# water_counter.net
KiCad netlist of a schematic drawn in EasyEDA
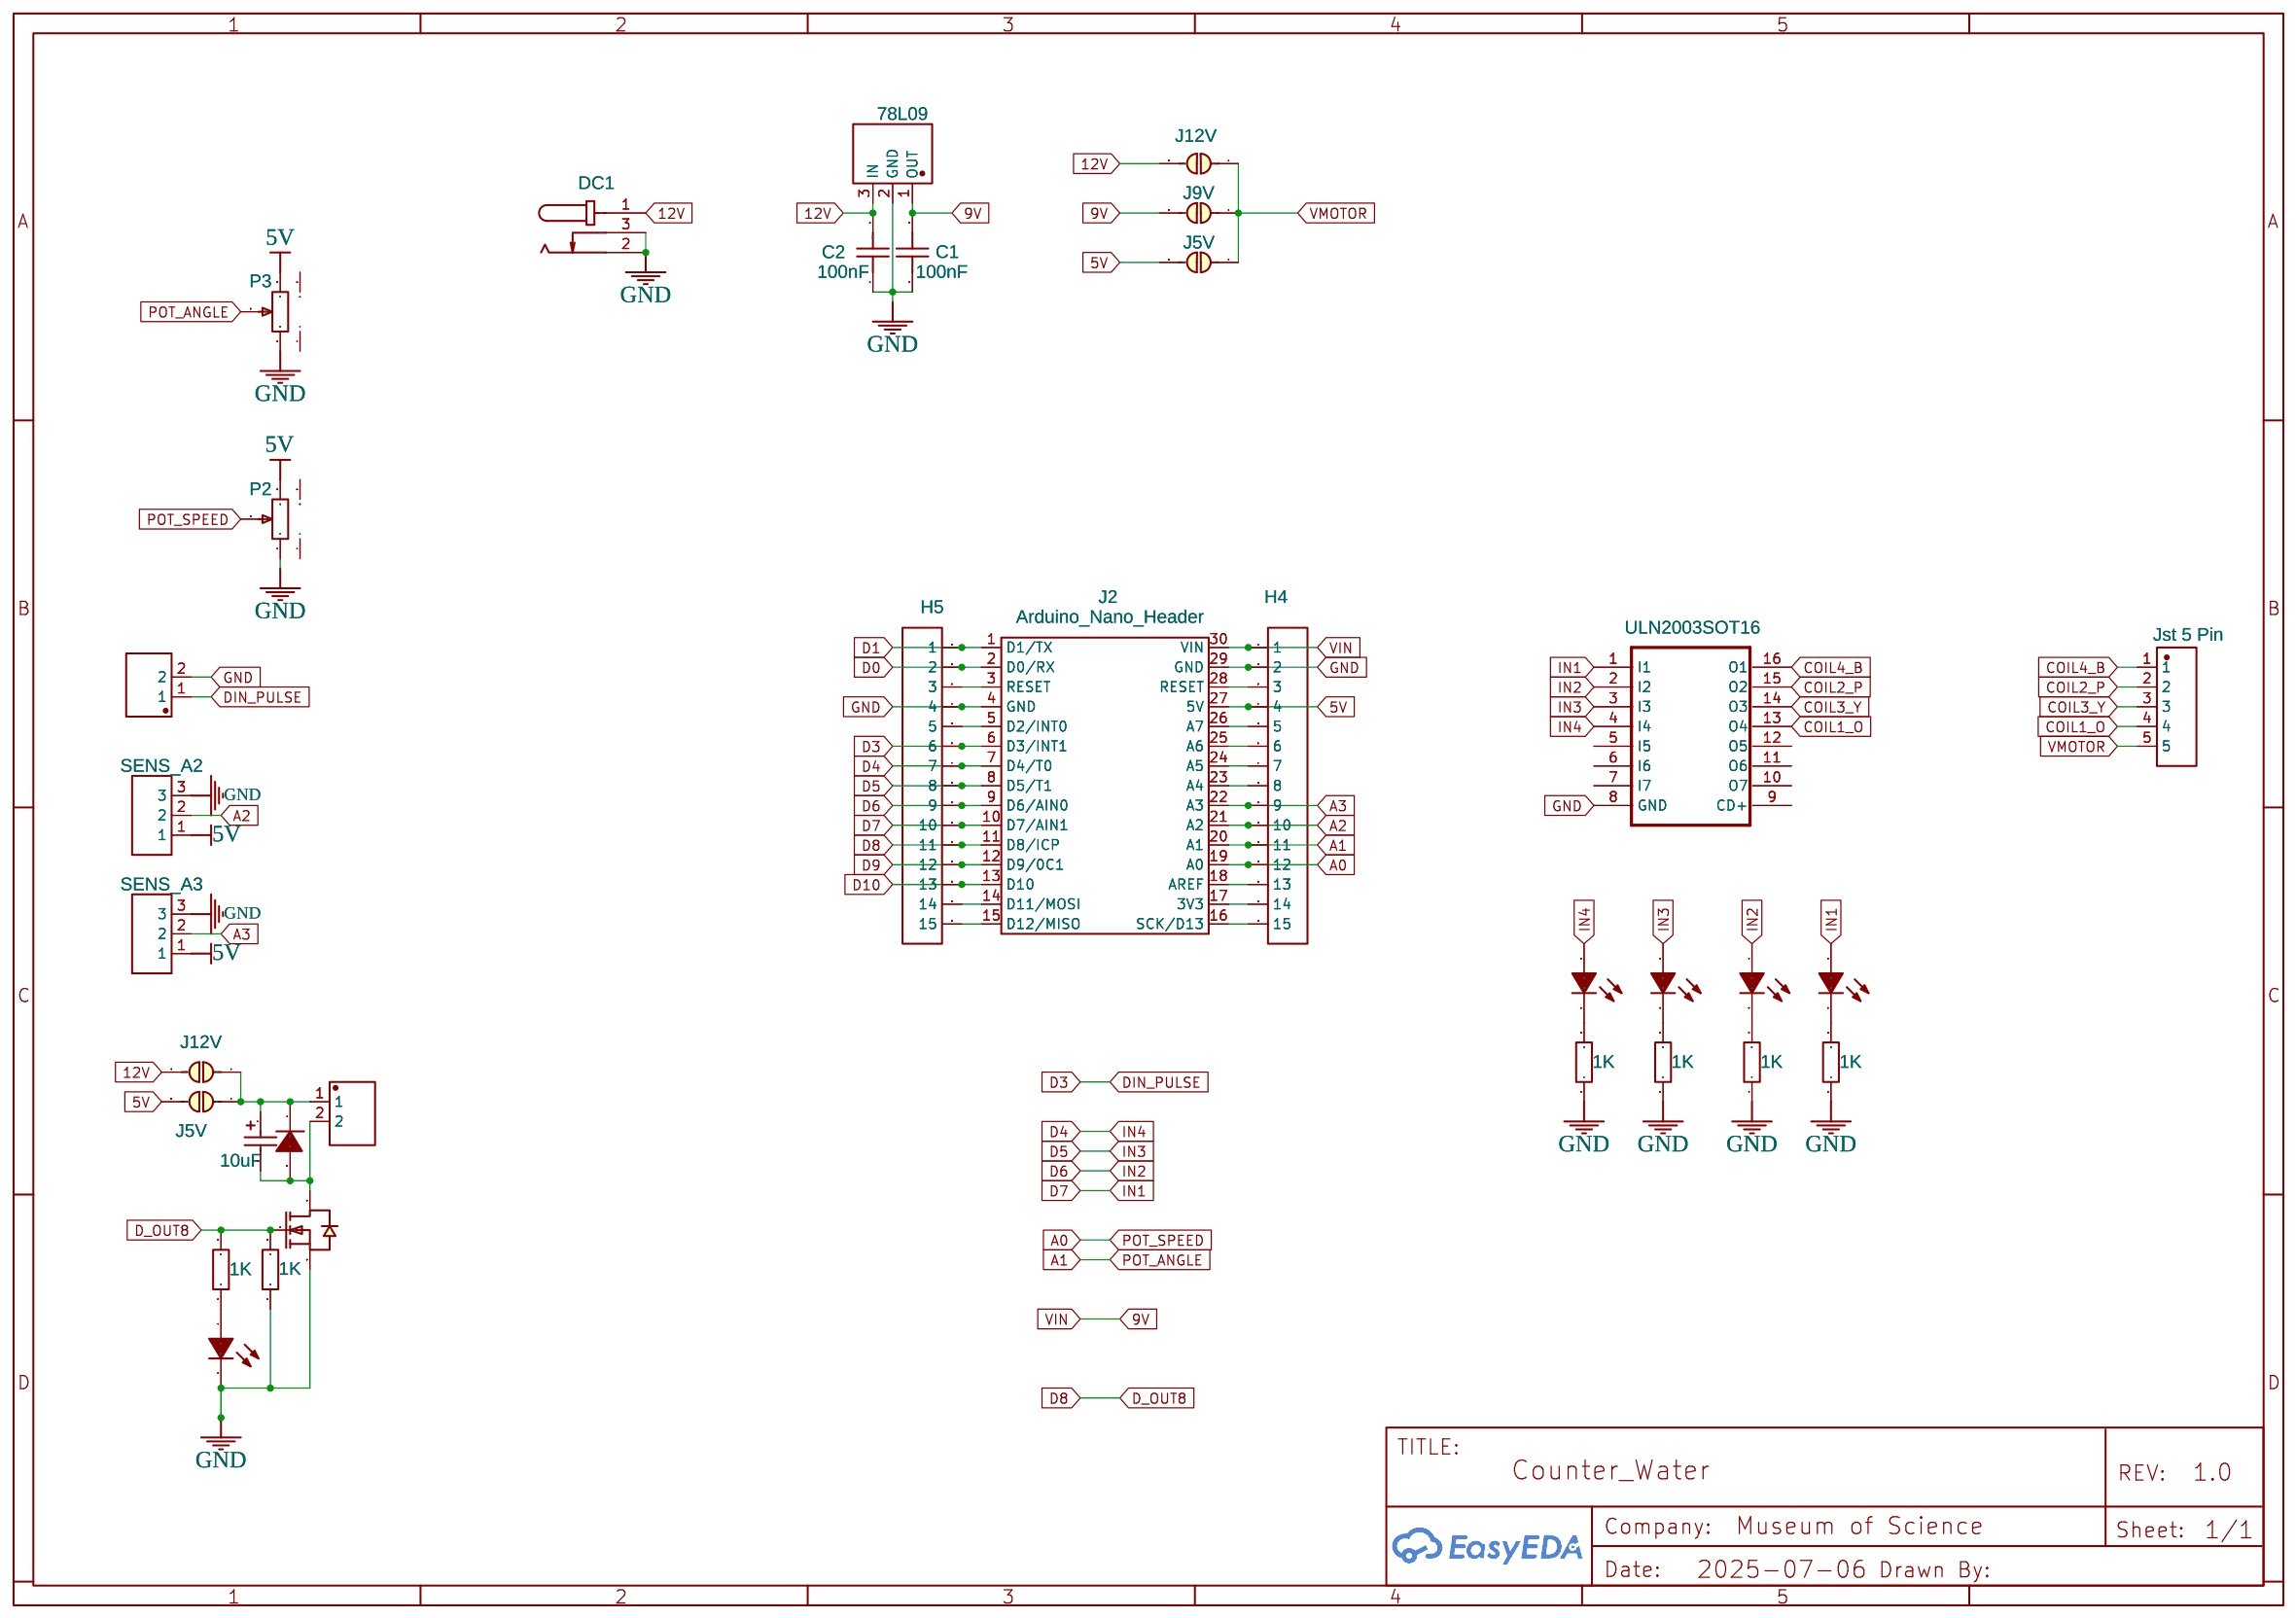
[diagram p0: schematic sheet]

(export (version "E")
  (design (tool "Eeschema 10.0.6"))
  (components
    (comp (ref "C1") (value "100nF") (libsource (lib "") (part "CC0603KRX7R9BB104")))
    (comp (ref "C2") (value "100nF") (libsource (lib "") (part "CC0603KRX7R9BB104")))
    (comp (ref "D3_PULSE")
      (value "KF2510-2A")
      (fields (field (name "Manufacturer") "BOOMELE"))
      (libsource (lib "") (part "KF2510-2A_1"))
    )
    (comp (ref "DC1")
      (value "DC")
      (fields (field (name "Manufacturer Part") "DC005-2.0MM") (field (name "Manufacturer") "SOFNG"))
      (libsource (lib "") (part "DC005-2.0MM"))
    )
    (comp (ref "ECM1") (value "10uF") (libsource (lib "") (part "TAJA106K016RNJ")))
    (comp (ref "ECON1")
      (value "D_OUT8")
      (fields (field (name "Manufacturer Part") "KF2510-2A") (field (name "Manufacturer") "BOOMELE"))
      (libsource (lib "") (part "KF2510-2A"))
    )
    (comp (ref "EDM1")
      (value "1N4007")
      (fields (field (name "Manufacturer Part") "1N4007F") (field (name "Manufacturer") "SK"))
      (libsource (lib "") (part "1N4007F"))
    )
    (comp (ref "ELD1")
      (value "LED")
      (fields
        (field (name "Manufacturer Part") "19-217/BHC-ZL1M2RY/3T")
        (field (name "Manufacturer") "EVERLIGHT")
      )
      (libsource (lib "") (part "19-217/BHC-ZL1M2RY/3T"))
    )
    (comp (ref "ELD2")
      (value "LED")
      (fields
        (field (name "Manufacturer Part") "19-217/BHC-ZL1M2RY/3T")
        (field (name "Manufacturer") "EVERLIGHT")
      )
      (libsource (lib "") (part "19-217/BHC-ZL1M2RY/3T"))
    )
    (comp (ref "ELD3")
      (value "LED")
      (fields
        (field (name "Manufacturer Part") "19-217/BHC-ZL1M2RY/3T")
        (field (name "Manufacturer") "EVERLIGHT")
      )
      (libsource (lib "") (part "19-217/BHC-ZL1M2RY/3T"))
    )
    (comp (ref "ELD4")
      (value "LED")
      (fields
        (field (name "Manufacturer Part") "19-217/BHC-ZL1M2RY/3T")
        (field (name "Manufacturer") "EVERLIGHT")
      )
      (libsource (lib "") (part "19-217/BHC-ZL1M2RY/3T"))
    )
    (comp (ref "ELD5")
      (value "LED")
      (fields
        (field (name "Manufacturer Part") "19-217/BHC-ZL1M2RY/3T")
        (field (name "Manufacturer") "EVERLIGHT")
      )
      (libsource (lib "") (part "19-217/BHC-ZL1M2RY/3T"))
    )
    (comp (ref "EQ1")
      (value "Q")
      (fields (field (name "Manufacturer Part") "AO3400") (field (name "Manufacturer") "ElecSuper(静芯微）"))
      (libsource (lib "") (part "JSM2302"))
    )
    (comp (ref "ERG1")
      (value "1K")
      (fields (field (name "Manufacturer Part") "0603WAF1001T5E") (field (name "Manufacturer") "UniOhm"))
      (libsource (lib "") (part "0603WAF1001T5E_1"))
    )
    (comp (ref "ERL1")
      (value "1K")
      (fields (field (name "Manufacturer Part") "0603WAF1001T5E") (field (name "Manufacturer") "UniOhm"))
      (libsource (lib "") (part "0603WAF1001T5E"))
    )
    (comp (ref "ERL2")
      (value "1K")
      (fields (field (name "Manufacturer Part") "0603WAF1001T5E") (field (name "Manufacturer") "UniOhm"))
      (libsource (lib "") (part "0603WAF1001T5E"))
    )
    (comp (ref "ERL3")
      (value "1K")
      (fields (field (name "Manufacturer Part") "0603WAF1001T5E") (field (name "Manufacturer") "UniOhm"))
      (libsource (lib "") (part "0603WAF1001T5E"))
    )
    (comp (ref "ERL4")
      (value "1K")
      (fields (field (name "Manufacturer Part") "0603WAF1001T5E") (field (name "Manufacturer") "UniOhm"))
      (libsource (lib "") (part "0603WAF1001T5E"))
    )
    (comp (ref "ERL5")
      (value "1K")
      (fields (field (name "Manufacturer Part") "0603WAF1001T5E") (field (name "Manufacturer") "UniOhm"))
      (libsource (lib "") (part "0603WAF1001T5E"))
    )
    (comp (ref "H4") (value "HDR-F-2.54_1x15") (libsource (lib "") (part "HDR-F-2.54_1x15_1")))
    (comp (ref "H5") (value "HDR-F-2.54_1x15") (libsource (lib "") (part "HDR-F-2.54_1x15")))
    (comp (ref "IC1") (value "ULN2003SOT16") (libsource (lib "") (part "ULN2003SOT16")))
    (comp (ref "J2") (value "Arduino_Nano_Header") (libsource (lib "") (part "Arduino_Nano_Header")))
    (comp (ref "J5V_1") (value "J5V") (libsource (lib "") (part "JUMPER-SMT_2_2")))
    (comp (ref "J5V_2") (value "J5V") (libsource (lib "") (part "JUMPER-SMT_2_2")))
    (comp (ref "J9V_1") (value "J9V") (libsource (lib "") (part "JUMPER-SMT_2_1")))
    (comp (ref "J12V_1") (value "J12V") (libsource (lib "") (part "JUMPER-SMT_2")))
    (comp (ref "J12V_2") (value "J12V") (libsource (lib "") (part "JUMPER-SMT_2")))
    (comp (ref "P2") (value "长柄旋转电位器") (libsource (lib "") (part "长柄旋转电位器")))
    (comp (ref "P3") (value "长柄旋转电位器") (libsource (lib "") (part "长柄旋转电位器")))
    (comp (ref "SENS_A2") (value "FK2510") (libsource (lib "") (part "kf2510_3A")))
    (comp (ref "SENS_A3") (value "FK2510") (libsource (lib "") (part "kf2510_3A")))
    (comp (ref "U1")
      (value "78L09")
      (fields (field (name "Manufacturer") "CBI(创基)"))
      (libsource (lib "") (part "78L09U 78L09"))
    )
    (comp (ref "U2")
      (value "Jst 5 Pin")
      (fields (field (name "Manufacturer") "Vicky"))
      (libsource (lib "") (part "Jst 5 Pin"))
    )
  )
  (nets
    (net (code "1") (name "5V") (class "Default")
      (node (ref "H4") (pin "4") (pinfunction "4_4") (pintype "unspecified"))
      (node (ref "J2") (pin "27") (pinfunction "5V_27") (pintype "unspecified"))
      (node (ref "J5V_1") (pin "2") (pinfunction "2_2") (pintype "bidirectional"))
      (node (ref "J5V_2") (pin "2") (pinfunction "2_2") (pintype "bidirectional"))
      (node (ref "P2") (pin "3") (pinfunction "3_3") (pintype "input"))
      (node (ref "P3") (pin "3") (pinfunction "3_3") (pintype "input"))
      (node (ref "SENS_A2") (pin "1") (pinfunction "1_1") (pintype "unspecified"))
      (node (ref "SENS_A3") (pin "1") (pinfunction "1_1") (pintype "unspecified"))
    )
    (net (code "2") (name "9V") (class "Default")
      (node (ref "C1") (pin "2") (pinfunction "2_2") (pintype "unspecified"))
      (node (ref "H4") (pin "1") (pinfunction "1_1") (pintype "unspecified"))
      (node (ref "J2") (pin "30") (pinfunction "VIN_30") (pintype "unspecified"))
      (node (ref "J9V_1") (pin "2") (pinfunction "2_2") (pintype "bidirectional"))
      (node (ref "U1") (pin "1") (pinfunction "OUT_1") (pintype "unspecified"))
    )
    (net (code "3") (name "12V") (class "Default")
      (node (ref "C2") (pin "2") (pinfunction "2_2") (pintype "unspecified"))
      (node (ref "DC1") (pin "1") (pinfunction "1_1") (pintype "unspecified"))
      (node (ref "J12V_1") (pin "2") (pinfunction "2_2") (pintype "bidirectional"))
      (node (ref "J12V_2") (pin "2") (pinfunction "2_2") (pintype "bidirectional"))
      (node (ref "U1") (pin "3") (pinfunction "IN_3") (pintype "unspecified"))
    )
    (net (code "4") (name "A0") (class "Default")
      (node (ref "H4") (pin "12") (pinfunction "12_12") (pintype "unspecified"))
      (node (ref "J2") (pin "19") (pinfunction "A0_19") (pintype "unspecified"))
      (node (ref "P2") (pin "2") (pinfunction "2_2") (pintype "input"))
    )
    (net (code "5") (name "A1") (class "Default")
      (node (ref "H4") (pin "11") (pinfunction "11_11") (pintype "unspecified"))
      (node (ref "J2") (pin "20") (pinfunction "A1_20") (pintype "unspecified"))
      (node (ref "P3") (pin "2") (pinfunction "2_2") (pintype "input"))
    )
    (net (code "6") (name "A2") (class "Default")
      (node (ref "H4") (pin "10") (pinfunction "10_10") (pintype "unspecified"))
      (node (ref "J2") (pin "21") (pinfunction "A2_21") (pintype "unspecified"))
      (node (ref "SENS_A2") (pin "2") (pinfunction "2_2") (pintype "unspecified"))
    )
    (net (code "7") (name "A3") (class "Default")
      (node (ref "H4") (pin "9") (pinfunction "9_9") (pintype "unspecified"))
      (node (ref "J2") (pin "22") (pinfunction "A3_22") (pintype "unspecified"))
      (node (ref "SENS_A3") (pin "2") (pinfunction "2_2") (pintype "unspecified"))
    )
    (net (code "8") (name "COIL1_O") (class "Default")
      (node (ref "IC1") (pin "13") (pinfunction "O4_13") (pintype "bidirectional"))
      (node (ref "U2") (pin "4") (pinfunction "4_4") (pintype "unspecified"))
    )
    (net (code "9") (name "COIL2_P") (class "Default")
      (node (ref "IC1") (pin "15") (pinfunction "O2_15") (pintype "bidirectional"))
      (node (ref "U2") (pin "2") (pinfunction "2_2") (pintype "unspecified"))
    )
    (net (code "10") (name "COIL3_Y") (class "Default")
      (node (ref "IC1") (pin "14") (pinfunction "O3_14") (pintype "bidirectional"))
      (node (ref "U2") (pin "3") (pinfunction "3_3") (pintype "unspecified"))
    )
    (net (code "11") (name "COIL4_B") (class "Default")
      (node (ref "IC1") (pin "16") (pinfunction "O1_16") (pintype "bidirectional"))
      (node (ref "U2") (pin "1") (pinfunction "1_1") (pintype "unspecified"))
    )
    (net (code "12") (name "D0") (class "Default")
      (node (ref "H5") (pin "2") (pinfunction "2_2") (pintype "unspecified"))
      (node (ref "J2") (pin "2") (pinfunction "D0/RX_2") (pintype "unspecified"))
    )
    (net (code "13") (name "D1") (class "Default")
      (node (ref "H5") (pin "1") (pinfunction "1_1") (pintype "unspecified"))
      (node (ref "J2") (pin "1") (pinfunction "D1/TX_1") (pintype "unspecified"))
    )
    (net (code "14") (name "D3") (class "Default")
      (node (ref "D3_PULSE") (pin "1") (pinfunction "1_1") (pintype "unspecified"))
      (node (ref "H5") (pin "6") (pinfunction "6_6") (pintype "unspecified"))
      (node (ref "J2") (pin "6") (pinfunction "D3/INT1_6") (pintype "unspecified"))
    )
    (net (code "15") (name "D4") (class "Default")
      (node (ref "ELD1") (pin "1") (pinfunction "A_1") (pintype "input"))
      (node (ref "H5") (pin "7") (pinfunction "7_7") (pintype "unspecified"))
      (node (ref "IC1") (pin "4") (pinfunction "I4_4") (pintype "bidirectional"))
      (node (ref "J2") (pin "7") (pinfunction "D4/T0_7") (pintype "unspecified"))
    )
    (net (code "16") (name "D5") (class "Default")
      (node (ref "ELD4") (pin "1") (pinfunction "A_1") (pintype "input"))
      (node (ref "H5") (pin "8") (pinfunction "8_8") (pintype "unspecified"))
      (node (ref "IC1") (pin "3") (pinfunction "I3_3") (pintype "bidirectional"))
      (node (ref "J2") (pin "8") (pinfunction "D5/T1_8") (pintype "unspecified"))
    )
    (net (code "17") (name "D6") (class "Default")
      (node (ref "ELD2") (pin "1") (pinfunction "A_1") (pintype "input"))
      (node (ref "H5") (pin "9") (pinfunction "9_9") (pintype "unspecified"))
      (node (ref "IC1") (pin "2") (pinfunction "I2_2") (pintype "bidirectional"))
      (node (ref "J2") (pin "9") (pinfunction "D6/AIN0_9") (pintype "unspecified"))
    )
    (net (code "18") (name "D7") (class "Default")
      (node (ref "ELD3") (pin "1") (pinfunction "A_1") (pintype "input"))
      (node (ref "H5") (pin "10") (pinfunction "10_10") (pintype "unspecified"))
      (node (ref "IC1") (pin "1") (pinfunction "I1_1") (pintype "bidirectional"))
      (node (ref "J2") (pin "10") (pinfunction "D7/AIN1_10") (pintype "unspecified"))
    )
    (net (code "19") (name "D8") (class "Default")
      (node (ref "EQ1") (pin "1") (pinfunction "G_1") (pintype "unspecified"))
      (node (ref "ERG1") (pin "2") (pinfunction "2_2") (pintype "input"))
      (node (ref "ERL5") (pin "2") (pinfunction "2_2") (pintype "input"))
      (node (ref "H5") (pin "11") (pinfunction "11_11") (pintype "unspecified"))
      (node (ref "J2") (pin "11") (pinfunction "D8/ICP_11") (pintype "unspecified"))
    )
    (net (code "20") (name "D9") (class "Default")
      (node (ref "H5") (pin "12") (pinfunction "12_12") (pintype "unspecified"))
      (node (ref "J2") (pin "12") (pinfunction "D9/0C1_12") (pintype "unspecified"))
    )
    (net (code "21") (name "D10") (class "Default")
      (node (ref "H5") (pin "13") (pinfunction "13_13") (pintype "unspecified"))
      (node (ref "J2") (pin "13") (pinfunction "D10_13") (pintype "unspecified"))
    )
    (net (code "22") (name "GND") (class "Default")
      (node (ref "C1") (pin "1") (pinfunction "1_1") (pintype "unspecified"))
      (node (ref "C2") (pin "1") (pinfunction "1_1") (pintype "unspecified"))
      (node (ref "D3_PULSE") (pin "2") (pinfunction "2_2") (pintype "unspecified"))
      (node (ref "DC1") (pin "2") (pinfunction "2_2") (pintype "unspecified"))
      (node (ref "DC1") (pin "3") (pinfunction "3_3") (pintype "unspecified"))
      (node (ref "ELD5") (pin "2") (pinfunction "C_2") (pintype "input"))
      (node (ref "EQ1") (pin "2") (pinfunction "S_2") (pintype "unspecified"))
      (node (ref "ERG1") (pin "1") (pinfunction "1_1") (pintype "input"))
      (node (ref "ERL1") (pin "1") (pinfunction "1_1") (pintype "input"))
      (node (ref "ERL2") (pin "1") (pinfunction "1_1") (pintype "input"))
      (node (ref "ERL3") (pin "1") (pinfunction "1_1") (pintype "input"))
      (node (ref "ERL4") (pin "1") (pinfunction "1_1") (pintype "input"))
      (node (ref "H4") (pin "2") (pinfunction "2_2") (pintype "unspecified"))
      (node (ref "H5") (pin "4") (pinfunction "4_4") (pintype "unspecified"))
      (node (ref "IC1") (pin "8") (pinfunction "GND_8") (pintype "bidirectional"))
      (node (ref "J2") (pin "29") (pinfunction "GND_29") (pintype "unspecified"))
      (node (ref "J2") (pin "4") (pinfunction "GND_4") (pintype "unspecified"))
      (node (ref "P2") (pin "1") (pinfunction "1_1") (pintype "input"))
      (node (ref "P3") (pin "1") (pinfunction "1_1") (pintype "input"))
      (node (ref "SENS_A2") (pin "3") (pinfunction "3_3") (pintype "unspecified"))
      (node (ref "SENS_A3") (pin "3") (pinfunction "3_3") (pintype "unspecified"))
      (node (ref "U1") (pin "2") (pinfunction "GND_2") (pintype "unspecified"))
    )
    (net (code "23") (name "Net-(EDM1-A)") (class "Default")
      (node (ref "ECM1") (pin "2") (pinfunction "2_2") (pintype "input"))
      (node (ref "ECON1") (pin "2") (pinfunction "2_2") (pintype "unspecified"))
      (node (ref "EDM1") (pin "2") (pinfunction "A_2") (pintype "unspecified"))
      (node (ref "EQ1") (pin "3") (pinfunction "D_3") (pintype "unspecified"))
    )
    (net (code "24") (name "Net-(EDM1-C)") (class "Default")
      (node (ref "ECM1") (pin "1") (pinfunction "1_1") (pintype "input"))
      (node (ref "ECON1") (pin "1") (pinfunction "1_1") (pintype "unspecified"))
      (node (ref "EDM1") (pin "1") (pinfunction "C_1") (pintype "unspecified"))
      (node (ref "J12V_2") (pin "1") (pinfunction "1_1") (pintype "bidirectional"))
      (node (ref "J5V_2") (pin "1") (pinfunction "1_1") (pintype "bidirectional"))
    )
    (net (code "25") (name "Net-(ELD1-C)") (class "Default")
      (node (ref "ELD1") (pin "2") (pinfunction "C_2") (pintype "input"))
      (node (ref "ERL1") (pin "2") (pinfunction "2_2") (pintype "input"))
    )
    (net (code "26") (name "Net-(ELD2-C)") (class "Default")
      (node (ref "ELD2") (pin "2") (pinfunction "C_2") (pintype "input"))
      (node (ref "ERL2") (pin "2") (pinfunction "2_2") (pintype "input"))
    )
    (net (code "27") (name "Net-(ELD3-C)") (class "Default")
      (node (ref "ELD3") (pin "2") (pinfunction "C_2") (pintype "input"))
      (node (ref "ERL3") (pin "2") (pinfunction "2_2") (pintype "input"))
    )
    (net (code "28") (name "Net-(ELD4-C)") (class "Default")
      (node (ref "ELD4") (pin "2") (pinfunction "C_2") (pintype "input"))
      (node (ref "ERL4") (pin "2") (pinfunction "2_2") (pintype "input"))
    )
    (net (code "29") (name "Net-(ELD5-A)") (class "Default")
      (node (ref "ELD5") (pin "1") (pinfunction "A_1") (pintype "input"))
      (node (ref "ERL5") (pin "1") (pinfunction "1_1") (pintype "input"))
    )
    (net (code "30") (name "Net-(H4-Pad3)") (class "Default")
      (node (ref "H4") (pin "3") (pinfunction "3_3") (pintype "unspecified"))
      (node (ref "J2") (pin "28") (pinfunction "RESET_28") (pintype "unspecified"))
    )
    (net (code "31") (name "Net-(H5-Pad3)") (class "Default")
      (node (ref "H5") (pin "3") (pinfunction "3_3") (pintype "unspecified"))
      (node (ref "J2") (pin "3") (pinfunction "RESET_3") (pintype "unspecified"))
    )
    (net (code "32") (name "Net-(J2-3V3)") (class "Default")
      (node (ref "H4") (pin "14") (pinfunction "14_14") (pintype "unspecified"))
      (node (ref "J2") (pin "17") (pinfunction "3V3_17") (pintype "unspecified"))
    )
    (net (code "33") (name "Net-(J2-A4)") (class "Default")
      (node (ref "H4") (pin "8") (pinfunction "8_8") (pintype "unspecified"))
      (node (ref "J2") (pin "23") (pinfunction "A4_23") (pintype "unspecified"))
    )
    (net (code "34") (name "Net-(J2-A5)") (class "Default")
      (node (ref "H4") (pin "7") (pinfunction "7_7") (pintype "unspecified"))
      (node (ref "J2") (pin "24") (pinfunction "A5_24") (pintype "unspecified"))
    )
    (net (code "35") (name "Net-(J2-A6)") (class "Default")
      (node (ref "H4") (pin "6") (pinfunction "6_6") (pintype "unspecified"))
      (node (ref "J2") (pin "25") (pinfunction "A6_25") (pintype "unspecified"))
    )
    (net (code "36") (name "Net-(J2-A7)") (class "Default")
      (node (ref "H4") (pin "5") (pinfunction "5_5") (pintype "unspecified"))
      (node (ref "J2") (pin "26") (pinfunction "A7_26") (pintype "unspecified"))
    )
    (net (code "37") (name "Net-(J2-AREF)") (class "Default")
      (node (ref "H4") (pin "13") (pinfunction "13_13") (pintype "unspecified"))
      (node (ref "J2") (pin "18") (pinfunction "AREF_18") (pintype "unspecified"))
    )
    (net (code "38") (name "Net-(J2-D2{slash}INT0)") (class "Default")
      (node (ref "H5") (pin "5") (pinfunction "5_5") (pintype "unspecified"))
      (node (ref "J2") (pin "5") (pinfunction "D2/INT0_5") (pintype "unspecified"))
    )
    (net (code "39") (name "Net-(J2-D11{slash}MOSI)") (class "Default")
      (node (ref "H5") (pin "14") (pinfunction "14_14") (pintype "unspecified"))
      (node (ref "J2") (pin "14") (pinfunction "D11/MOSI_14") (pintype "unspecified"))
    )
    (net (code "40") (name "Net-(J2-D12{slash}MISO)") (class "Default")
      (node (ref "H5") (pin "15") (pinfunction "15_15") (pintype "unspecified"))
      (node (ref "J2") (pin "15") (pinfunction "D12/MISO_15") (pintype "unspecified"))
    )
    (net (code "41") (name "Net-(J2-SCK{slash}D13)") (class "Default")
      (node (ref "H4") (pin "15") (pinfunction "15_15") (pintype "unspecified"))
      (node (ref "J2") (pin "16") (pinfunction "SCK/D13_16") (pintype "unspecified"))
    )
    (net (code "42") (name "VMOTOR") (class "Default")
      (node (ref "J12V_1") (pin "1") (pinfunction "1_1") (pintype "bidirectional"))
      (node (ref "J5V_1") (pin "1") (pinfunction "1_1") (pintype "bidirectional"))
      (node (ref "J9V_1") (pin "1") (pinfunction "1_1") (pintype "bidirectional"))
      (node (ref "U2") (pin "5") (pinfunction "5_5") (pintype "unspecified"))
    )
    (net (code "43") (name "unconnected-(IC1-CD+-Pad9)") (class "Default")
      (node (ref "IC1") (pin "9") (pinfunction "CD+_9") (pintype "bidirectional"))
    )
    (net (code "44") (name "unconnected-(IC1-I5-Pad5)") (class "Default")
      (node (ref "IC1") (pin "5") (pinfunction "I5_5") (pintype "bidirectional"))
    )
    (net (code "45") (name "unconnected-(IC1-I6-Pad6)") (class "Default")
      (node (ref "IC1") (pin "6") (pinfunction "I6_6") (pintype "bidirectional"))
    )
    (net (code "46") (name "unconnected-(IC1-I7-Pad7)") (class "Default")
      (node (ref "IC1") (pin "7") (pinfunction "I7_7") (pintype "bidirectional"))
    )
    (net (code "47") (name "unconnected-(IC1-O5-Pad12)") (class "Default")
      (node (ref "IC1") (pin "12") (pinfunction "O5_12") (pintype "bidirectional"))
    )
    (net (code "48") (name "unconnected-(IC1-O6-Pad11)") (class "Default")
      (node (ref "IC1") (pin "11") (pinfunction "O6_11") (pintype "bidirectional"))
    )
    (net (code "49") (name "unconnected-(IC1-O7-Pad10)") (class "Default")
      (node (ref "IC1") (pin "10") (pinfunction "O7_10") (pintype "bidirectional"))
    )
    (net (code "50") (name "unconnected-(P2-Pad4)") (class "Default")
      (node (ref "P2") (pin "4") (pinfunction "4_4") (pintype "input"))
    )
    (net (code "51") (name "unconnected-(P2-Pad5)") (class "Default")
      (node (ref "P2") (pin "5") (pinfunction "5_5") (pintype "input"))
    )
    (net (code "52") (name "unconnected-(P3-Pad4)") (class "Default")
      (node (ref "P3") (pin "4") (pinfunction "4_4") (pintype "input"))
    )
    (net (code "53") (name "unconnected-(P3-Pad5)") (class "Default")
      (node (ref "P3") (pin "5") (pinfunction "5_5") (pintype "input"))
    )
  )
)
